# expansion-dualdrive.net
KiCad netlist of a schematic drawn in EAGLE
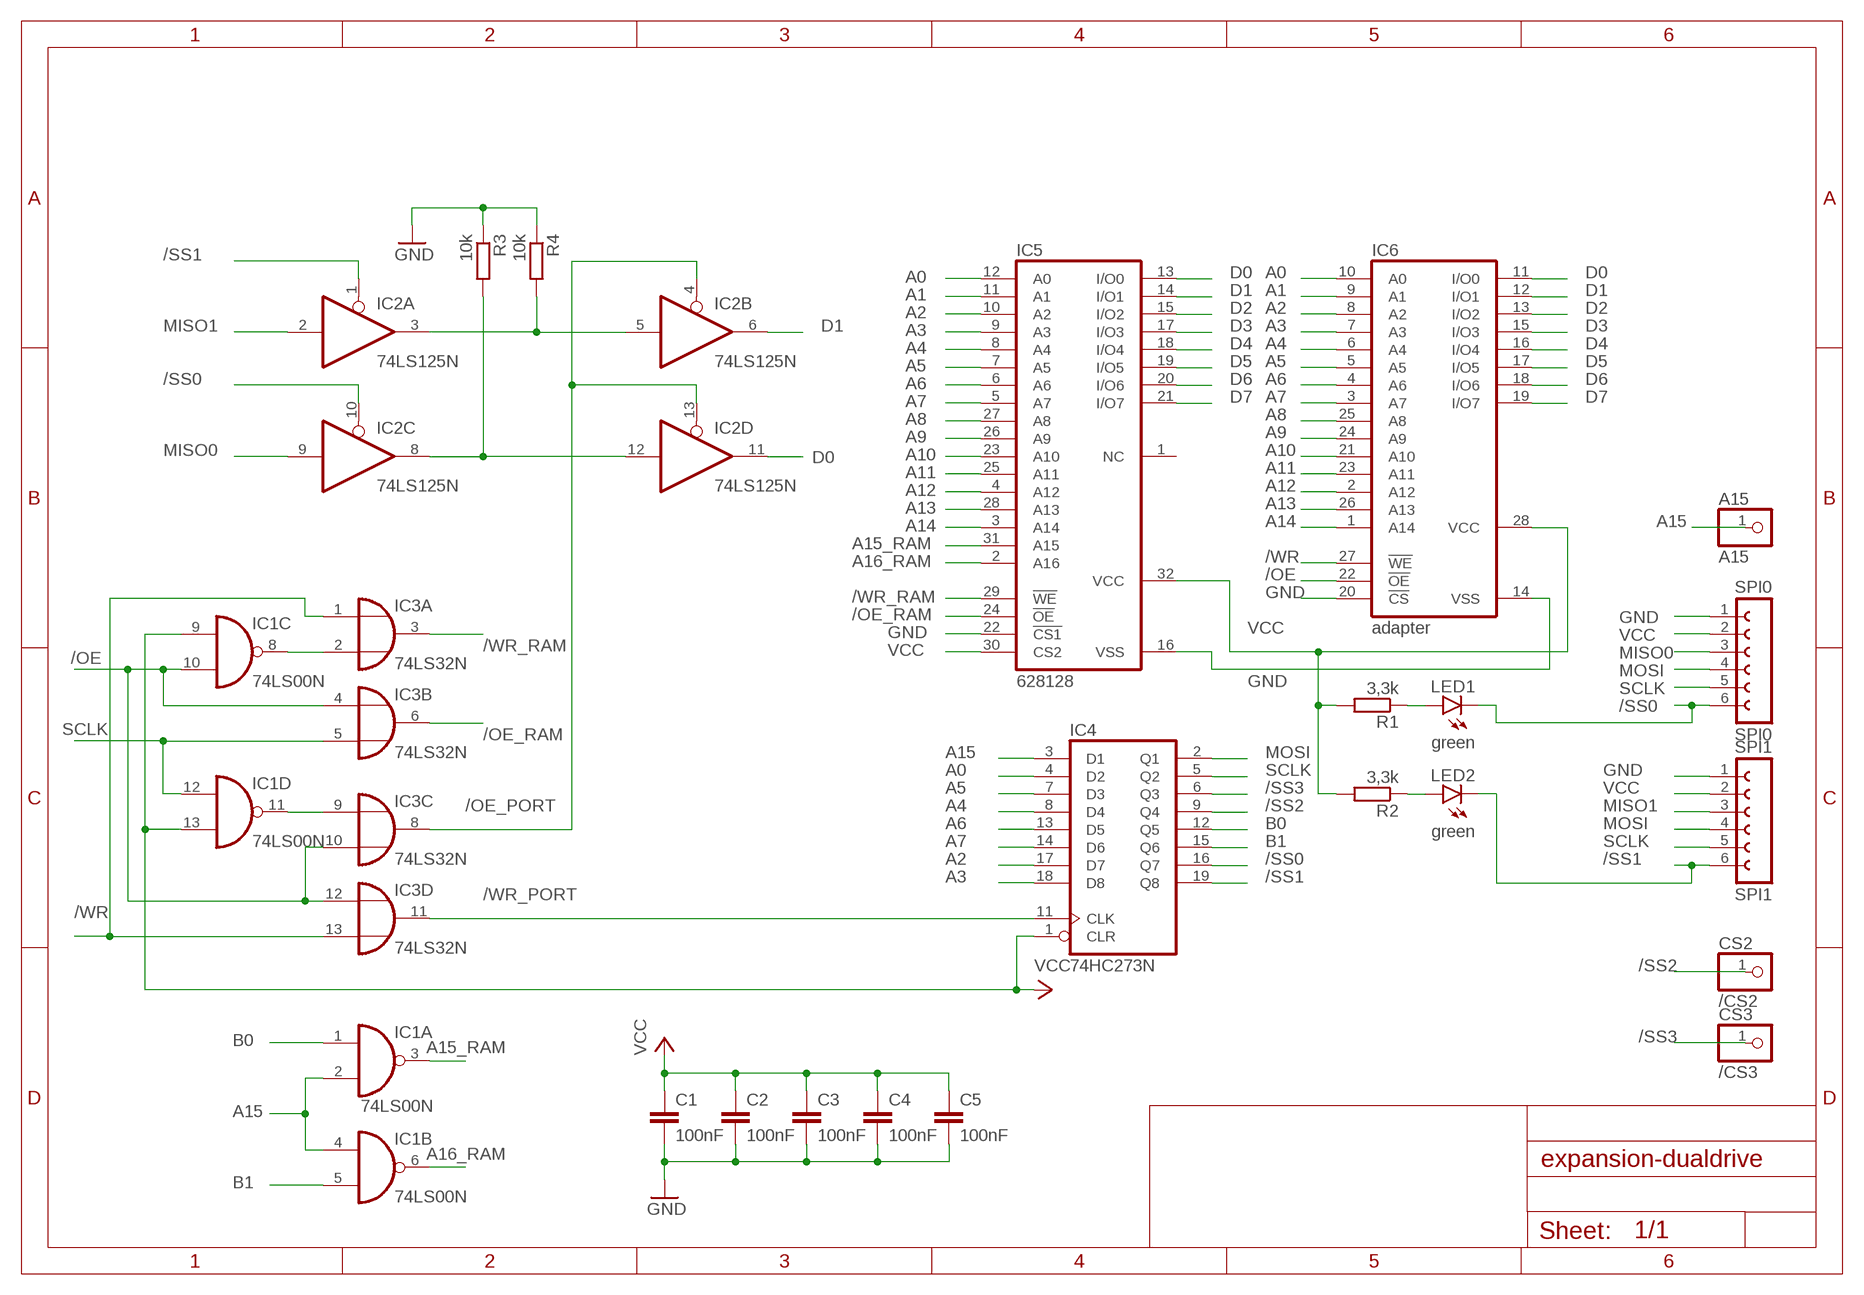
[diagram p0: schematic, sheet 1]

(export (version "E")
  (design (tool "Eeschema 10.0.6"))
  (components
    (comp (ref "A15")
      (value "A15")
      (footprint "eagle-import:1X01")
      (libsource (lib "eagle-import") (part "PINHD-1X1"))
    )
    (comp (ref "C1")
      (value "100nF")
      (footprint "eagle-import:C050-024X044")
      (libsource (lib "eagle-import") (part "C-EU050-024X044"))
    )
    (comp (ref "C2")
      (value "100nF")
      (footprint "eagle-import:C050-024X044")
      (libsource (lib "eagle-import") (part "C-EU050-024X044"))
    )
    (comp (ref "C3")
      (value "100nF")
      (footprint "eagle-import:C050-024X044")
      (libsource (lib "eagle-import") (part "C-EU050-024X044"))
    )
    (comp (ref "C4")
      (value "100nF")
      (footprint "eagle-import:C050-024X044")
      (libsource (lib "eagle-import") (part "C-EU050-024X044"))
    )
    (comp (ref "C5")
      (value "100nF")
      (footprint "eagle-import:C050-024X044")
      (libsource (lib "eagle-import") (part "C-EU050-024X044"))
    )
    (comp (ref "CS2")
      (value "/CS2")
      (footprint "eagle-import:1X01")
      (libsource (lib "eagle-import") (part "PINHD-1X1"))
    )
    (comp (ref "CS3")
      (value "/CS3")
      (footprint "eagle-import:1X01")
      (libsource (lib "eagle-import") (part "PINHD-1X1"))
    )
    (comp (ref "IC1")
      (value "74LS00N")
      (footprint "eagle-import:DIL14")
      (libsource (lib "eagle-import") (part "7400NLS"))
    )
    (comp (ref "IC2")
      (value "74LS125N")
      (footprint "eagle-import:DIL14")
      (libsource (lib "eagle-import") (part "74125NLS"))
    )
    (comp (ref "IC3")
      (value "74LS32N")
      (footprint "eagle-import:DIL14")
      (libsource (lib "eagle-import") (part "7432NLS"))
    )
    (comp (ref "IC4")
      (value "74HC273N")
      (footprint "eagle-import:DIL20")
      (libsource (lib "eagle-import") (part "74273NHC"))
    )
    (comp (ref "IC5")
      (value "628128")
      (footprint "eagle-import:DIL32")
      (libsource (lib "eagle-import") (part "628128P"))
    )
    (comp (ref "IC6")
      (value "adapter")
      (footprint "eagle-import:DIL28-6")
      (libsource (lib "eagle-import") (part "62256P"))
    )
    (comp (ref "LED1")
      (value "green")
      (footprint "eagle-import:LED3MM")
      (libsource (lib "eagle-import") (part "LED3MM"))
    )
    (comp (ref "LED2")
      (value "green")
      (footprint "eagle-import:LED3MM")
      (libsource (lib "eagle-import") (part "LED3MM"))
    )
    (comp (ref "R1")
      (value "3,3k")
      (footprint "eagle-import:0207_10")
      (libsource (lib "eagle-import") (part "R-EU_0207/10"))
    )
    (comp (ref "R2")
      (value "3,3k")
      (footprint "eagle-import:0207_10")
      (libsource (lib "eagle-import") (part "R-EU_0207/10"))
    )
    (comp (ref "R3")
      (value "10k")
      (footprint "eagle-import:0207_10")
      (libsource (lib "eagle-import") (part "R-EU_0207/10"))
    )
    (comp (ref "R4")
      (value "10k")
      (footprint "eagle-import:0207_10")
      (libsource (lib "eagle-import") (part "R-EU_0207/10"))
    )
    (comp (ref "SPI0")
      (value "SPI0")
      (footprint "eagle-import:FE06")
      (libsource (lib "eagle-import") (part "FE06-1"))
    )
    (comp (ref "SPI1")
      (value "SPI1")
      (footprint "eagle-import:FE06")
      (libsource (lib "eagle-import") (part "FE06-1"))
    )
  )
  (nets
    (net (code "1") (name "/A0") (class "Default")
      (node (ref "IC4") (pin "4") (pinfunction "D2_4") (pintype "input"))
      (node (ref "IC5") (pin "12") (pinfunction "A0_12") (pintype "input"))
      (node (ref "IC6") (pin "10") (pinfunction "A0_10") (pintype "input"))
    )
    (net (code "2") (name "/A1") (class "Default")
      (node (ref "IC5") (pin "11") (pinfunction "A1_11") (pintype "input"))
      (node (ref "IC6") (pin "9") (pinfunction "A1_9") (pintype "input"))
    )
    (net (code "3") (name "/A2") (class "Default")
      (node (ref "IC4") (pin "17") (pinfunction "D7_17") (pintype "input"))
      (node (ref "IC5") (pin "10") (pinfunction "A2_10") (pintype "input"))
      (node (ref "IC6") (pin "8") (pinfunction "A2_8") (pintype "input"))
    )
    (net (code "4") (name "/A3") (class "Default")
      (node (ref "IC4") (pin "18") (pinfunction "D8_18") (pintype "input"))
      (node (ref "IC5") (pin "9") (pinfunction "A3_9") (pintype "input"))
      (node (ref "IC6") (pin "7") (pinfunction "A3_7") (pintype "input"))
    )
    (net (code "5") (name "/A4") (class "Default")
      (node (ref "IC4") (pin "8") (pinfunction "D4_8") (pintype "input"))
      (node (ref "IC5") (pin "8") (pinfunction "A4_8") (pintype "input"))
      (node (ref "IC6") (pin "6") (pinfunction "A4_6") (pintype "input"))
    )
    (net (code "6") (name "/A5") (class "Default")
      (node (ref "IC4") (pin "7") (pinfunction "D3_7") (pintype "input"))
      (node (ref "IC5") (pin "7") (pinfunction "A5_7") (pintype "input"))
      (node (ref "IC6") (pin "5") (pinfunction "A5_5") (pintype "input"))
    )
    (net (code "7") (name "/A6") (class "Default")
      (node (ref "IC4") (pin "13") (pinfunction "D5_13") (pintype "input"))
      (node (ref "IC5") (pin "6") (pinfunction "A6_6") (pintype "input"))
      (node (ref "IC6") (pin "4") (pinfunction "A6_4") (pintype "input"))
    )
    (net (code "8") (name "/A7") (class "Default")
      (node (ref "IC4") (pin "14") (pinfunction "D6_14") (pintype "input"))
      (node (ref "IC5") (pin "5") (pinfunction "A7_5") (pintype "input"))
      (node (ref "IC6") (pin "3") (pinfunction "A7_3") (pintype "input"))
    )
    (net (code "9") (name "/A8") (class "Default")
      (node (ref "IC5") (pin "27") (pinfunction "A8_27") (pintype "input"))
      (node (ref "IC6") (pin "25") (pinfunction "A8_25") (pintype "input"))
    )
    (net (code "10") (name "/A9") (class "Default")
      (node (ref "IC5") (pin "26") (pinfunction "A9_26") (pintype "input"))
      (node (ref "IC6") (pin "24") (pinfunction "A9_24") (pintype "input"))
    )
    (net (code "11") (name "/A10") (class "Default")
      (node (ref "IC5") (pin "23") (pinfunction "A10_23") (pintype "input"))
      (node (ref "IC6") (pin "21") (pinfunction "A10_21") (pintype "input"))
    )
    (net (code "12") (name "/A11") (class "Default")
      (node (ref "IC5") (pin "25") (pinfunction "A11_25") (pintype "input"))
      (node (ref "IC6") (pin "23") (pinfunction "A11_23") (pintype "input"))
    )
    (net (code "13") (name "/A12") (class "Default")
      (node (ref "IC5") (pin "4") (pinfunction "A12_4") (pintype "input"))
      (node (ref "IC6") (pin "2") (pinfunction "A12_2") (pintype "input"))
    )
    (net (code "14") (name "/A13") (class "Default")
      (node (ref "IC5") (pin "28") (pinfunction "A13_28") (pintype "input"))
      (node (ref "IC6") (pin "26") (pinfunction "A13_26") (pintype "input"))
    )
    (net (code "15") (name "/A14") (class "Default")
      (node (ref "IC5") (pin "3") (pinfunction "A14_3") (pintype "input"))
      (node (ref "IC6") (pin "1") (pinfunction "A14_1") (pintype "input"))
    )
    (net (code "16") (name "/A15") (class "Default")
      (node (ref "A15") (pin "1") (pinfunction "1_1") (pintype "passive"))
      (node (ref "IC1") (pin "2") (pinfunction "I1_2") (pintype "input"))
      (node (ref "IC1") (pin "4") (pinfunction "I0_4") (pintype "input"))
      (node (ref "IC4") (pin "3") (pinfunction "D1_3") (pintype "input"))
    )
    (net (code "17") (name "/A15_RAM") (class "Default")
      (node (ref "IC1") (pin "3") (pinfunction "O_3") (pintype "output"))
      (node (ref "IC5") (pin "31") (pinfunction "A15_31") (pintype "input"))
    )
    (net (code "18") (name "/A16_RAM") (class "Default")
      (node (ref "IC1") (pin "6") (pinfunction "O_6") (pintype "output"))
      (node (ref "IC5") (pin "2") (pinfunction "A16_2") (pintype "input"))
    )
    (net (code "19") (name "/B0") (class "Default")
      (node (ref "IC1") (pin "1") (pinfunction "I0_1") (pintype "input"))
      (node (ref "IC4") (pin "12") (pinfunction "Q5_12") (pintype "output"))
    )
    (net (code "20") (name "/B1") (class "Default")
      (node (ref "IC1") (pin "5") (pinfunction "I1_5") (pintype "input"))
      (node (ref "IC4") (pin "15") (pinfunction "Q6_15") (pintype "output"))
    )
    (net (code "21") (name "/D0") (class "Default")
      (node (ref "IC2") (pin "11") (pinfunction "O_11") (pintype "tri_state"))
      (node (ref "IC5") (pin "13") (pinfunction "I/O0_13") (pintype "bidirectional"))
      (node (ref "IC6") (pin "11") (pinfunction "I/O0_11") (pintype "bidirectional"))
    )
    (net (code "22") (name "/D1") (class "Default")
      (node (ref "IC2") (pin "6") (pinfunction "O_6") (pintype "tri_state"))
      (node (ref "IC5") (pin "14") (pinfunction "I/O1_14") (pintype "bidirectional"))
      (node (ref "IC6") (pin "12") (pinfunction "I/O1_12") (pintype "bidirectional"))
    )
    (net (code "23") (name "/D2") (class "Default")
      (node (ref "IC5") (pin "15") (pinfunction "I/O2_15") (pintype "bidirectional"))
      (node (ref "IC6") (pin "13") (pinfunction "I/O2_13") (pintype "bidirectional"))
    )
    (net (code "24") (name "/D3") (class "Default")
      (node (ref "IC5") (pin "17") (pinfunction "I/O3_17") (pintype "bidirectional"))
      (node (ref "IC6") (pin "15") (pinfunction "I/O3_15") (pintype "bidirectional"))
    )
    (net (code "25") (name "/D4") (class "Default")
      (node (ref "IC5") (pin "18") (pinfunction "I/O4_18") (pintype "bidirectional"))
      (node (ref "IC6") (pin "16") (pinfunction "I/O4_16") (pintype "bidirectional"))
    )
    (net (code "26") (name "/D5") (class "Default")
      (node (ref "IC5") (pin "19") (pinfunction "I/O5_19") (pintype "bidirectional"))
      (node (ref "IC6") (pin "17") (pinfunction "I/O5_17") (pintype "bidirectional"))
    )
    (net (code "27") (name "/D6") (class "Default")
      (node (ref "IC5") (pin "20") (pinfunction "I/O6_20") (pintype "bidirectional"))
      (node (ref "IC6") (pin "18") (pinfunction "I/O6_18") (pintype "bidirectional"))
    )
    (net (code "28") (name "/D7") (class "Default")
      (node (ref "IC5") (pin "21") (pinfunction "I/O7_21") (pintype "bidirectional"))
      (node (ref "IC6") (pin "19") (pinfunction "I/O7_19") (pintype "bidirectional"))
    )
    (net (code "29") (name "/MISO0") (class "Default")
      (node (ref "IC2") (pin "9") (pinfunction "I_9") (pintype "input"))
      (node (ref "SPI0") (pin "3") (pinfunction "3_3") (pintype "passive"))
    )
    (net (code "30") (name "/MISO1") (class "Default")
      (node (ref "IC2") (pin "2") (pinfunction "I_2") (pintype "input"))
      (node (ref "SPI1") (pin "3") (pinfunction "3_3") (pintype "passive"))
    )
    (net (code "31") (name "/MOSI") (class "Default")
      (node (ref "IC4") (pin "2") (pinfunction "Q1_2") (pintype "output"))
      (node (ref "SPI0") (pin "4") (pinfunction "4_4") (pintype "passive"))
      (node (ref "SPI1") (pin "4") (pinfunction "4_4") (pintype "passive"))
    )
    (net (code "32") (name "/SCLK") (class "Default")
      (node (ref "IC1") (pin "12") (pinfunction "I0_12") (pintype "input"))
      (node (ref "IC3") (pin "5") (pinfunction "I1_5") (pintype "input"))
      (node (ref "IC4") (pin "5") (pinfunction "Q2_5") (pintype "output"))
      (node (ref "SPI0") (pin "5") (pinfunction "5_5") (pintype "passive"))
      (node (ref "SPI1") (pin "5") (pinfunction "5_5") (pintype "passive"))
    )
    (net (code "33") (name "/{slash}OE") (class "Default")
      (node (ref "IC1") (pin "10") (pinfunction "I1_10") (pintype "input"))
      (node (ref "IC3") (pin "10") (pinfunction "I1_10") (pintype "input"))
      (node (ref "IC3") (pin "12") (pinfunction "I0_12") (pintype "input"))
      (node (ref "IC3") (pin "4") (pinfunction "I0_4") (pintype "input"))
      (node (ref "IC6") (pin "22") (pinfunction "~{OE}_22") (pintype "input"))
    )
    (net (code "34") (name "/{slash}OE_PORT") (class "Default")
      (node (ref "IC2") (pin "13") (pinfunction "OE_13") (pintype "input"))
      (node (ref "IC2") (pin "4") (pinfunction "OE_4") (pintype "input"))
      (node (ref "IC3") (pin "8") (pinfunction "O_8") (pintype "output"))
    )
    (net (code "35") (name "/{slash}OE_RAM") (class "Default")
      (node (ref "IC3") (pin "6") (pinfunction "O_6") (pintype "output"))
      (node (ref "IC5") (pin "24") (pinfunction "~{OE}_24") (pintype "input"))
    )
    (net (code "36") (name "/{slash}SS0") (class "Default")
      (node (ref "IC2") (pin "10") (pinfunction "OE_10") (pintype "input"))
      (node (ref "IC4") (pin "16") (pinfunction "Q7_16") (pintype "output"))
      (node (ref "LED1") (pin "K") (pinfunction "C_K") (pintype "passive"))
      (node (ref "SPI0") (pin "6") (pinfunction "6_6") (pintype "passive"))
    )
    (net (code "37") (name "/{slash}SS1") (class "Default")
      (node (ref "IC2") (pin "1") (pinfunction "OE_1") (pintype "input"))
      (node (ref "IC4") (pin "19") (pinfunction "Q8_19") (pintype "output"))
      (node (ref "LED2") (pin "K") (pinfunction "C_K") (pintype "passive"))
      (node (ref "SPI1") (pin "6") (pinfunction "6_6") (pintype "passive"))
    )
    (net (code "38") (name "/{slash}SS2") (class "Default")
      (node (ref "CS2") (pin "1") (pinfunction "1_1") (pintype "passive"))
      (node (ref "IC4") (pin "9") (pinfunction "Q4_9") (pintype "output"))
    )
    (net (code "39") (name "/{slash}SS3") (class "Default")
      (node (ref "CS3") (pin "1") (pinfunction "1_1") (pintype "passive"))
      (node (ref "IC4") (pin "6") (pinfunction "Q3_6") (pintype "output"))
    )
    (net (code "40") (name "/{slash}WR") (class "Default")
      (node (ref "IC3") (pin "1") (pinfunction "I0_1") (pintype "input"))
      (node (ref "IC3") (pin "13") (pinfunction "I1_13") (pintype "input"))
      (node (ref "IC6") (pin "27") (pinfunction "~{WE}_27") (pintype "input"))
    )
    (net (code "41") (name "/{slash}WR_PORT") (class "Default")
      (node (ref "IC3") (pin "11") (pinfunction "O_11") (pintype "output"))
      (node (ref "IC4") (pin "11") (pinfunction "CLK_11") (pintype "input"))
    )
    (net (code "42") (name "/{slash}WR_RAM") (class "Default")
      (node (ref "IC3") (pin "3") (pinfunction "O_3") (pintype "output"))
      (node (ref "IC5") (pin "29") (pinfunction "~{WE}_29") (pintype "input"))
    )
    (net (code "43") (name "GND") (class "Default")
      (node (ref "C1") (pin "2") (pinfunction "2_2") (pintype "passive"))
      (node (ref "C2") (pin "2") (pinfunction "2_2") (pintype "passive"))
      (node (ref "C3") (pin "2") (pinfunction "2_2") (pintype "passive"))
      (node (ref "C4") (pin "2") (pinfunction "2_2") (pintype "passive"))
      (node (ref "C5") (pin "2") (pinfunction "2_2") (pintype "passive"))
      (node (ref "IC5") (pin "16") (pinfunction "VSS_16") (pintype "power_in"))
      (node (ref "IC5") (pin "22") (pinfunction "~{CS1}_22") (pintype "input"))
      (node (ref "IC6") (pin "14") (pinfunction "VSS_14") (pintype "power_in"))
      (node (ref "IC6") (pin "20") (pinfunction "~{CS}_20") (pintype "input"))
      (node (ref "R3") (pin "1") (pinfunction "1_1") (pintype "passive"))
      (node (ref "R4") (pin "1") (pinfunction "1_1") (pintype "passive"))
      (node (ref "SPI0") (pin "1") (pinfunction "1_1") (pintype "passive"))
      (node (ref "SPI1") (pin "1") (pinfunction "1_1") (pintype "passive"))
    )
    (net (code "44") (name "Net-(IC1C-O)") (class "Default")
      (node (ref "IC1") (pin "8") (pinfunction "O_8") (pintype "output"))
      (node (ref "IC3") (pin "2") (pinfunction "I1_2") (pintype "input"))
    )
    (net (code "45") (name "Net-(IC1D-O)") (class "Default")
      (node (ref "IC1") (pin "11") (pinfunction "O_11") (pintype "output"))
      (node (ref "IC3") (pin "9") (pinfunction "I0_9") (pintype "input"))
    )
    (net (code "46") (name "Net-(IC2A-O)") (class "Default")
      (node (ref "IC2") (pin "3") (pinfunction "O_3") (pintype "tri_state"))
      (node (ref "IC2") (pin "5") (pinfunction "I_5") (pintype "input"))
      (node (ref "R4") (pin "2") (pinfunction "2_2") (pintype "passive"))
    )
    (net (code "47") (name "Net-(IC2C-O)") (class "Default")
      (node (ref "IC2") (pin "12") (pinfunction "I_12") (pintype "input"))
      (node (ref "IC2") (pin "8") (pinfunction "O_8") (pintype "tri_state"))
      (node (ref "R3") (pin "2") (pinfunction "2_2") (pintype "passive"))
    )
    (net (code "48") (name "Net-(LED1-PadA)") (class "Default")
      (node (ref "LED1") (pin "A") (pinfunction "A_A") (pintype "passive"))
      (node (ref "R1") (pin "1") (pinfunction "1_1") (pintype "passive"))
    )
    (net (code "49") (name "Net-(LED2-PadA)") (class "Default")
      (node (ref "LED2") (pin "A") (pinfunction "A_A") (pintype "passive"))
      (node (ref "R2") (pin "1") (pinfunction "1_1") (pintype "passive"))
    )
    (net (code "50") (name "VCC") (class "Default")
      (node (ref "C1") (pin "1") (pinfunction "1_1") (pintype "passive"))
      (node (ref "C2") (pin "1") (pinfunction "1_1") (pintype "passive"))
      (node (ref "C3") (pin "1") (pinfunction "1_1") (pintype "passive"))
      (node (ref "C4") (pin "1") (pinfunction "1_1") (pintype "passive"))
      (node (ref "C5") (pin "1") (pinfunction "1_1") (pintype "passive"))
      (node (ref "IC1") (pin "13") (pinfunction "I1_13") (pintype "input"))
      (node (ref "IC1") (pin "9") (pinfunction "I0_9") (pintype "input"))
      (node (ref "IC4") (pin "1") (pinfunction "CLR_1") (pintype "input"))
      (node (ref "IC5") (pin "30") (pinfunction "CS2_30") (pintype "input"))
      (node (ref "IC5") (pin "32") (pinfunction "VCC_32") (pintype "power_in"))
      (node (ref "IC6") (pin "28") (pinfunction "VCC_28") (pintype "power_in"))
      (node (ref "R1") (pin "2") (pinfunction "2_2") (pintype "passive"))
      (node (ref "R2") (pin "2") (pinfunction "2_2") (pintype "passive"))
      (node (ref "SPI0") (pin "2") (pinfunction "2_2") (pintype "passive"))
      (node (ref "SPI1") (pin "2") (pinfunction "2_2") (pintype "passive"))
    )
    (net (code "51") (name "unconnected-(IC5-NC-Pad1)") (class "Default")
      (node (ref "IC5") (pin "1") (pinfunction "NC_1") (pintype "no_connect"))
    )
  )
)
